# Rain_Alert_System.net
KiCad netlist of a schematic drawn in EAGLE
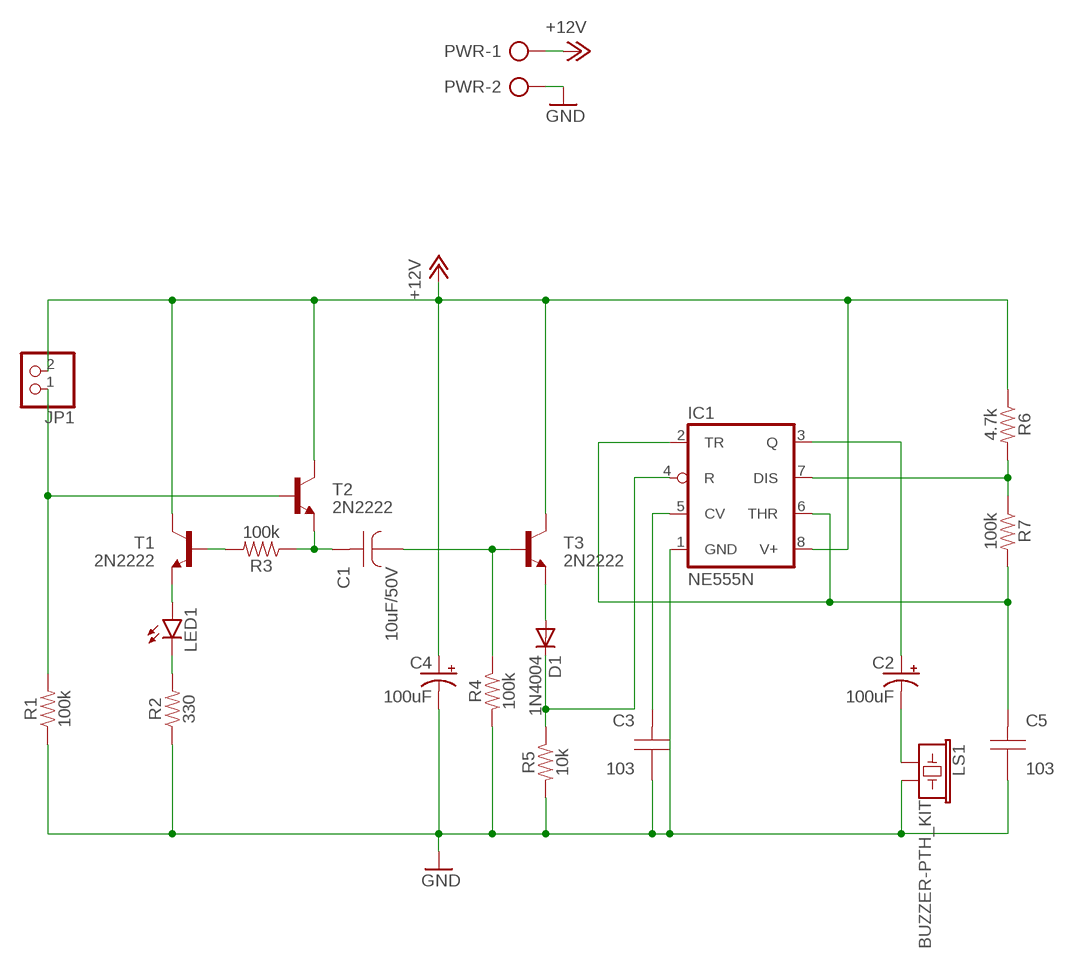
[diagram p0: schematic, sheet 1]

(export (version "E")
  (design (tool "Eeschema 10.0.6"))
  (components
    (comp (ref "C1")
      (value "10uF/50V")
      (footprint "eagle-import:D5")
      (libsource (lib "eagle-import") (part "10UF/50V"))
    )
    (comp (ref "C2")
      (value "100uF")
      (footprint "eagle-import:CPOL-RADIAL-2.5MM-6.5MM")
      (libsource (lib "eagle-import") (part "100UF-POLAR-RADIAL-2.5MM-25V-20%"))
    )
    (comp (ref "C3")
      (value "103")
      (footprint "eagle-import:P2.8")
      (libsource (lib "eagle-import") (part "100NFP2.8"))
    )
    (comp (ref "C4")
      (value "100uF")
      (footprint "eagle-import:CPOL-RADIAL-2.5MM-6.5MM")
      (libsource (lib "eagle-import") (part "100UF-POLAR-RADIAL-2.5MM-25V-20%"))
    )
    (comp (ref "C5")
      (value "103")
      (footprint "eagle-import:P2.8")
      (libsource (lib "eagle-import") (part "100NFP2.8"))
    )
    (comp (ref "D1")
      (value "1N4004")
      (footprint "eagle-import:DO41-10")
      (libsource (lib "eagle-import") (part "1N4004"))
    )
    (comp (ref "IC1")
      (value "NE555N")
      (footprint "eagle-import:DIL08-ROUND")
      (libsource (lib "eagle-import") (part "555NNE"))
    )
    (comp (ref "JP1")
      (value "PINHD-1X2/90")
      (footprint "eagle-import:1X02_90")
      (libsource (lib "eagle-import") (part "PINHD-1X2/90"))
    )
    (comp (ref "LED1")
      (value "LED5MM")
      (footprint "eagle-import:LED5MM")
      (libsource (lib "eagle-import") (part "LED5MM"))
    )
    (comp (ref "LS1")
      (value "BUZZER-PTH_KIT")
      (footprint "eagle-import:BUZZER-12MM-KIT")
      (libsource (lib "eagle-import") (part "BUZZER-PTH_KIT"))
    )
    (comp (ref "PWR") (value "2P") (footprint "eagle-import:2P") (libsource (lib "eagle-import") (part "2P")))
    (comp (ref "R1")
      (value "100k")
      (footprint "eagle-import:AXIAL-0.3")
      (libsource (lib "eagle-import") (part "RESISTORAXIAL-0.3"))
    )
    (comp (ref "R2")
      (value "330")
      (footprint "eagle-import:AXIAL-0.3")
      (libsource (lib "eagle-import") (part "RESISTORAXIAL-0.3"))
    )
    (comp (ref "R3")
      (value "100k")
      (footprint "eagle-import:AXIAL-0.3")
      (libsource (lib "eagle-import") (part "RESISTORAXIAL-0.3"))
    )
    (comp (ref "R4")
      (value "100k")
      (footprint "eagle-import:AXIAL-0.3")
      (libsource (lib "eagle-import") (part "RESISTORAXIAL-0.3"))
    )
    (comp (ref "R5")
      (value "10k")
      (footprint "eagle-import:AXIAL-0.3")
      (libsource (lib "eagle-import") (part "RESISTORAXIAL-0.3"))
    )
    (comp (ref "R6")
      (value "4.7k")
      (footprint "eagle-import:AXIAL-0.3")
      (libsource (lib "eagle-import") (part "RESISTORAXIAL-0.3"))
    )
    (comp (ref "R7")
      (value "100k")
      (footprint "eagle-import:AXIAL-0.3")
      (libsource (lib "eagle-import") (part "RESISTORAXIAL-0.3"))
    )
    (comp (ref "T1")
      (value "2N2222")
      (footprint "eagle-import:TO92-EBC-OVAL")
      (libsource (lib "eagle-import") (part "2N2222"))
    )
    (comp (ref "T2")
      (value "2N2222")
      (footprint "eagle-import:TO92-EBC-OVAL")
      (libsource (lib "eagle-import") (part "2N2222"))
    )
    (comp (ref "T3")
      (value "2N2222")
      (footprint "eagle-import:TO92-EBC-OVAL")
      (libsource (lib "eagle-import") (part "2N2222"))
    )
  )
  (nets
    (net (code "1") (name "+12V") (class "Default")
      (node (ref "C4") (pin "1") (pinfunction "+_1") (pintype "passive"))
      (node (ref "IC1") (pin "8") (pinfunction "V+_8") (pintype "power_in"))
      (node (ref "JP1") (pin "2") (pinfunction "2_2") (pintype "passive"))
      (node (ref "PWR") (pin "1") (pinfunction "KL_1") (pintype "passive"))
      (node (ref "R6") (pin "P$1") (pinfunction "1_P$1") (pintype "passive"))
      (node (ref "T1") (pin "C") (pinfunction "C_C") (pintype "passive"))
      (node (ref "T2") (pin "C") (pinfunction "C_C") (pintype "passive"))
      (node (ref "T3") (pin "C") (pinfunction "C_C") (pintype "passive"))
    )
    (net (code "2") (name "GND") (class "Default")
      (node (ref "C3") (pin "2") (pinfunction "K1_2") (pintype "bidirectional"))
      (node (ref "C4") (pin "2") (pinfunction "-_2") (pintype "passive"))
      (node (ref "C5") (pin "2") (pinfunction "K1_2") (pintype "bidirectional"))
      (node (ref "IC1") (pin "1") (pinfunction "GND_1") (pintype "power_in"))
      (node (ref "LS1") (pin "-") (pinfunction "2_-") (pintype "passive"))
      (node (ref "PWR") (pin "2") (pinfunction "KL_2") (pintype "passive"))
      (node (ref "R1") (pin "P$1") (pinfunction "1_P$1") (pintype "passive"))
      (node (ref "R2") (pin "P$1") (pinfunction "1_P$1") (pintype "passive"))
      (node (ref "R4") (pin "P$2") (pinfunction "2_P$2") (pintype "passive"))
      (node (ref "R5") (pin "P$2") (pinfunction "2_P$2") (pintype "passive"))
    )
    (net (code "3") (name "Net-(C2-+)") (class "Default")
      (node (ref "C2") (pin "1") (pinfunction "+_1") (pintype "passive"))
      (node (ref "IC1") (pin "3") (pinfunction "Q_3") (pintype "output"))
    )
    (net (code "4") (name "Net-(C2--)") (class "Default")
      (node (ref "C2") (pin "2") (pinfunction "-_2") (pintype "passive"))
      (node (ref "LS1") (pin "+") (pinfunction "1_+") (pintype "passive"))
    )
    (net (code "5") (name "Net-(C3-A1)") (class "Default")
      (node (ref "C3") (pin "1") (pinfunction "A1_1") (pintype "bidirectional"))
      (node (ref "IC1") (pin "5") (pinfunction "CV_5") (pintype "input"))
    )
    (net (code "6") (name "Net-(C5-A1)") (class "Default")
      (node (ref "C5") (pin "1") (pinfunction "A1_1") (pintype "bidirectional"))
      (node (ref "IC1") (pin "2") (pinfunction "TR_2") (pintype "input"))
      (node (ref "IC1") (pin "6") (pinfunction "THR_6") (pintype "input"))
      (node (ref "R7") (pin "P$2") (pinfunction "2_P$2") (pintype "passive"))
    )
    (net (code "7") (name "Net-(D1-PadA)") (class "Default")
      (node (ref "D1") (pin "A") (pinfunction "A_A") (pintype "passive"))
      (node (ref "T3") (pin "E") (pinfunction "E_E") (pintype "passive"))
    )
    (net (code "8") (name "Net-(IC1-DIS)") (class "Default")
      (node (ref "IC1") (pin "7") (pinfunction "DIS_7") (pintype "input"))
      (node (ref "R6") (pin "P$2") (pinfunction "2_P$2") (pintype "passive"))
      (node (ref "R7") (pin "P$1") (pinfunction "1_P$1") (pintype "passive"))
    )
    (net (code "9") (name "Net-(IC1-R)") (class "Default")
      (node (ref "D1") (pin "C") (pinfunction "C_C") (pintype "passive"))
      (node (ref "IC1") (pin "4") (pinfunction "R_4") (pintype "input"))
      (node (ref "R5") (pin "P$1") (pinfunction "1_P$1") (pintype "passive"))
    )
    (net (code "10") (name "Net-(LED1-C)") (class "Default")
      (node (ref "LED1") (pin "K") (pinfunction "C_K") (pintype "passive"))
      (node (ref "R2") (pin "P$2") (pinfunction "2_P$2") (pintype "passive"))
    )
    (net (code "11") (name "Net-(LED1-PadA)") (class "Default")
      (node (ref "LED1") (pin "A") (pinfunction "A_A") (pintype "passive"))
      (node (ref "T1") (pin "E") (pinfunction "E_E") (pintype "passive"))
    )
    (net (code "12") (name "Net-(R1-2)") (class "Default")
      (node (ref "JP1") (pin "1") (pinfunction "1_1") (pintype "passive"))
      (node (ref "R1") (pin "P$2") (pinfunction "2_P$2") (pintype "passive"))
      (node (ref "T2") (pin "B") (pinfunction "B_B") (pintype "passive"))
    )
    (net (code "13") (name "Net-(R3-1)") (class "Default")
      (node (ref "C1") (pin "A") (pinfunction "A_A") (pintype "bidirectional"))
      (node (ref "R3") (pin "P$1") (pinfunction "1_P$1") (pintype "passive"))
      (node (ref "T2") (pin "E") (pinfunction "E_E") (pintype "passive"))
    )
    (net (code "14") (name "Net-(R3-2)") (class "Default")
      (node (ref "R3") (pin "P$2") (pinfunction "2_P$2") (pintype "passive"))
      (node (ref "T1") (pin "B") (pinfunction "B_B") (pintype "passive"))
    )
    (net (code "15") (name "Net-(R4-1)") (class "Default")
      (node (ref "C1") (pin "K") (pinfunction "K_K") (pintype "bidirectional"))
      (node (ref "R4") (pin "P$1") (pinfunction "1_P$1") (pintype "passive"))
      (node (ref "T3") (pin "B") (pinfunction "B_B") (pintype "passive"))
    )
  )
)
